# 01-100BASET1_PHY.net
KiCad netlist of a schematic drawn in Altium Designer
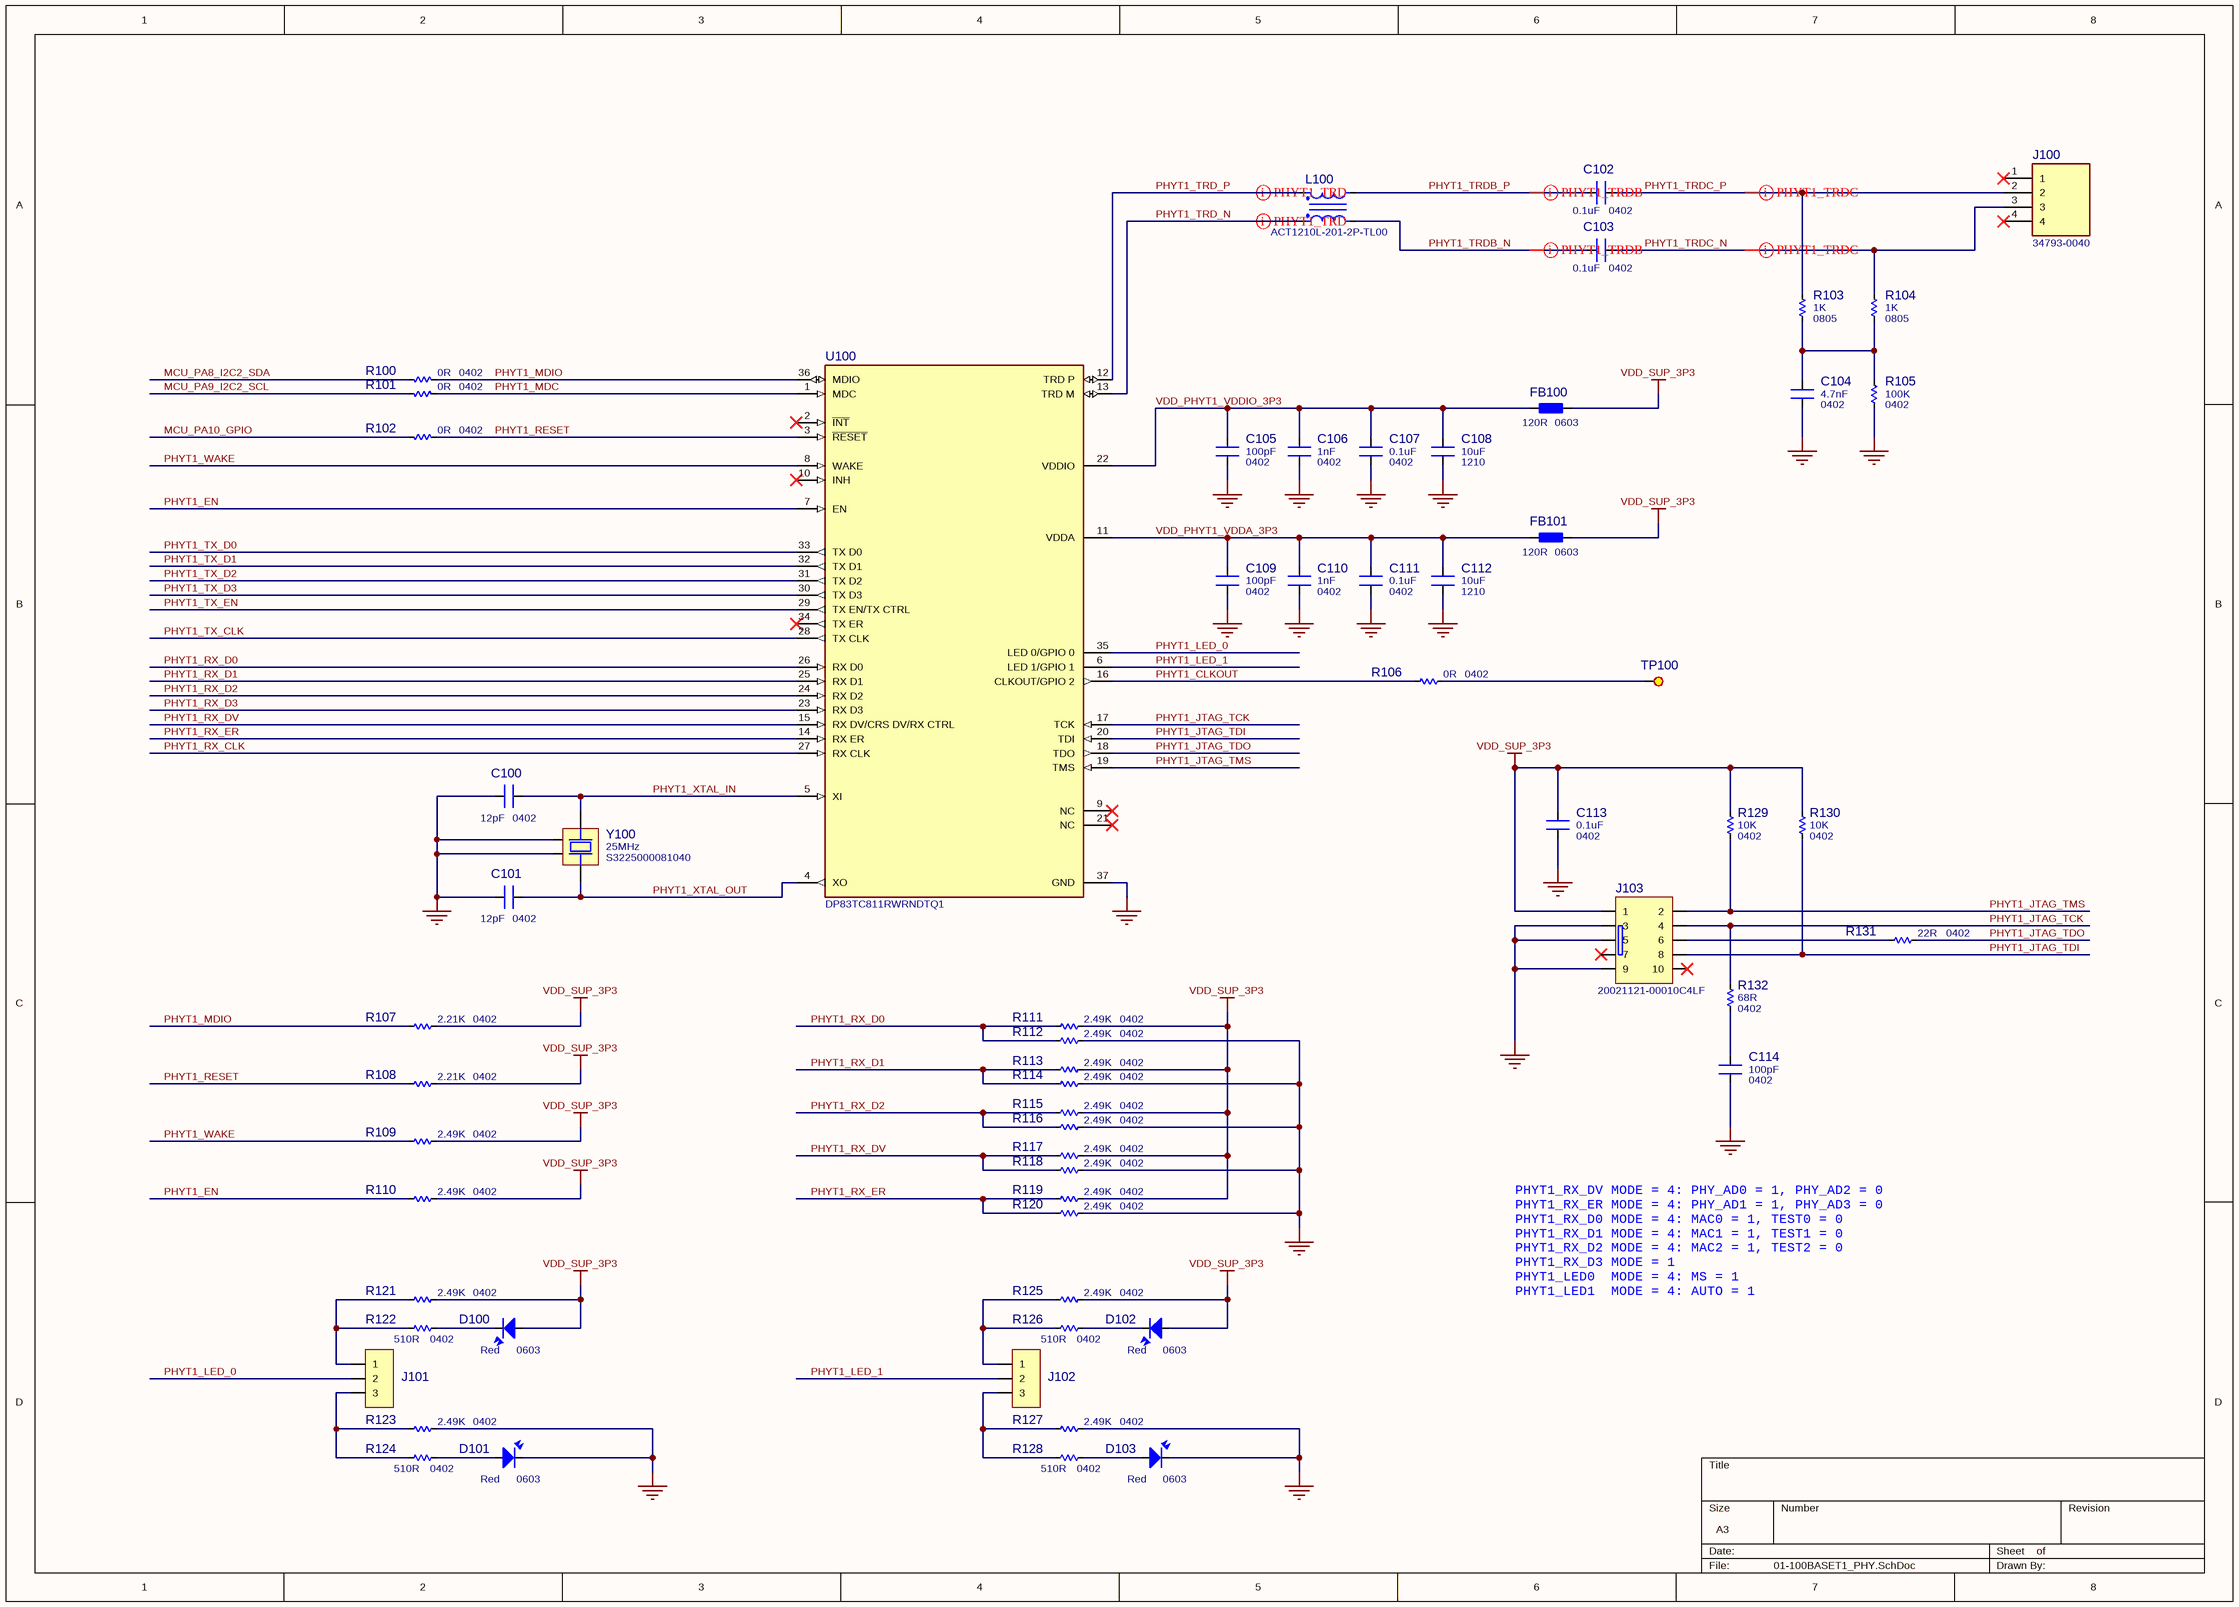
[diagram p0: 01-100BASET1_PHY.SchDoc]

(export (version "E")
  (design (tool "Eeschema 10.0.6"))
  (components
    (comp (ref "C100")
      (value "12pF")
      (footprint "CAP_C_0402")
      (description "Ceramic Capacitor SMD 0402 12pF ±5% 50V")
      (fields
        (field (name "TOLERANCE") "±5%")
        (field (name "MANUFACTURER") "FH(Guangdong Fenghua Advanced Tech)")
        (field (name "PACKAGE") "0402")
      )
      (libsource (lib "AS50") (part "Cap"))
    )
    (comp (ref "C101")
      (value "12pF")
      (footprint "CAP_C_0402")
      (description "Ceramic Capacitor SMD 0402 12pF ±5% 50V")
      (fields
        (field (name "TOLERANCE") "±5%")
        (field (name "MANUFACTURER") "FH(Guangdong Fenghua Advanced Tech)")
        (field (name "PACKAGE") "0402")
      )
      (libsource (lib "AS50") (part "Cap"))
    )
    (comp (ref "C102")
      (value "0.1uF")
      (footprint "CAP_C_0402")
      (description "Ceramic Capacitor SMD 0402 100nF ±10% 16V")
      (fields
        (field (name "TOLERANCE") "±10%")
        (field (name "MANUFACTURER") "Samsung")
        (field (name "PACKAGE") "0402")
      )
      (libsource (lib "AS50") (part "Cap"))
    )
    (comp (ref "C103")
      (value "0.1uF")
      (footprint "CAP_C_0402")
      (description "Ceramic Capacitor SMD 0402 100nF ±10% 16V")
      (fields
        (field (name "TOLERANCE") "±10%")
        (field (name "MANUFACTURER") "Samsung")
        (field (name "PACKAGE") "0402")
      )
      (libsource (lib "AS50") (part "Cap"))
    )
    (comp (ref "C104")
      (value "4.7nF")
      (footprint "CAP_C_0402")
      (description "Ceramic Capacitor SMD 0402 4.7nF ±10% 50V")
      (fields
        (field (name "TOLERANCE") "±10%")
        (field (name "MANUFACTURER") "FH(Guangdong Fenghua Advanced Tech)")
        (field (name "PACKAGE") "0402")
      )
      (libsource (lib "AS50") (part "Cap"))
    )
    (comp (ref "C105")
      (value "100pF")
      (footprint "CAP_C_0402")
      (description "Ceramic Capacitor SMD 0402 100pF ±5% 50V")
      (fields
        (field (name "TOLERANCE") "±5%")
        (field (name "MANUFACTURER") "Samsung")
        (field (name "PACKAGE") "0402")
      )
      (libsource (lib "AS50") (part "Cap"))
    )
    (comp (ref "C106")
      (value "1nF")
      (footprint "CAP_C_0402")
      (description "Ceramic Capacitor SMD 0402 1nF ±10% 50V")
      (fields
        (field (name "TOLERANCE") "±10%")
        (field (name "MANUFACTURER") "Samsung")
        (field (name "PACKAGE") "0402")
      )
      (libsource (lib "AS50") (part "Cap"))
    )
    (comp (ref "C107")
      (value "0.1uF")
      (footprint "CAP_C_0402")
      (description "Ceramic Capacitor SMD 0402 100nF ±10% 16V")
      (fields
        (field (name "TOLERANCE") "±10%")
        (field (name "MANUFACTURER") "Samsung")
        (field (name "PACKAGE") "0402")
      )
      (libsource (lib "AS50") (part "Cap"))
    )
    (comp (ref "C108")
      (value "10uF")
      (footprint "CAP_C_1210")
      (description "Ceramic Capacitor SMD 1210 10uF ±10% 25V")
      (fields
        (field (name "TOLERANCE") "±10%")
        (field (name "MANUFACTURER") "Samsung")
        (field (name "PACKAGE") "1210")
      )
      (libsource (lib "AS50") (part "Cap"))
    )
    (comp (ref "C109")
      (value "100pF")
      (footprint "CAP_C_0402")
      (description "Ceramic Capacitor SMD 0402 100pF ±5% 50V")
      (fields
        (field (name "TOLERANCE") "±5%")
        (field (name "MANUFACTURER") "Samsung")
        (field (name "PACKAGE") "0402")
      )
      (libsource (lib "AS50") (part "Cap"))
    )
    (comp (ref "C110")
      (value "1nF")
      (footprint "CAP_C_0402")
      (description "Ceramic Capacitor SMD 0402 1nF ±10% 50V")
      (fields
        (field (name "TOLERANCE") "±10%")
        (field (name "MANUFACTURER") "Samsung")
        (field (name "PACKAGE") "0402")
      )
      (libsource (lib "AS50") (part "Cap"))
    )
    (comp (ref "C111")
      (value "0.1uF")
      (footprint "CAP_C_0402")
      (description "Ceramic Capacitor SMD 0402 100nF ±10% 16V")
      (fields
        (field (name "TOLERANCE") "±10%")
        (field (name "MANUFACTURER") "Samsung")
        (field (name "PACKAGE") "0402")
      )
      (libsource (lib "AS50") (part "Cap"))
    )
    (comp (ref "C112")
      (value "10uF")
      (footprint "CAP_C_1210")
      (description "Ceramic Capacitor SMD 1210 10uF ±10% 25V")
      (fields
        (field (name "TOLERANCE") "±10%")
        (field (name "MANUFACTURER") "Samsung")
        (field (name "PACKAGE") "1210")
      )
      (libsource (lib "AS50") (part "Cap"))
    )
    (comp (ref "C113")
      (value "0.1uF")
      (footprint "CAP_C_0402")
      (description "Ceramic Capacitor SMD 0402 100nF ±10% 16V")
      (fields
        (field (name "TOLERANCE") "±10%")
        (field (name "MANUFACTURER") "Samsung")
        (field (name "PACKAGE") "0402")
      )
      (libsource (lib "AS50") (part "Cap"))
    )
    (comp (ref "C114")
      (value "100pF")
      (footprint "CAP_C_0402")
      (description "Ceramic Capacitor SMD 0402 100pF ±5% 50V")
      (fields
        (field (name "TOLERANCE") "±5%")
        (field (name "MANUFACTURER") "FH(Guangdong Fenghua Advanced Tech)")
        (field (name "PACKAGE") "0402")
      )
      (libsource (lib "AS50") (part "Cap"))
    )
    (comp (ref "D100")
      (value "LED")
      (footprint "LED-SMD-0603-RED")
      (description "Red 615~630nm 1.9~2.2V 0603 Light Emitting Diodes (LED) RoHS")
      (fields
        (field (name "MANUFACTURER") "Hubei KENTO Elec")
        (field (name "MANUFACTURER PART NUMBER") "KT-0603R")
        (field (name "COLOR") "Red")
        (field (name "PACKAGE") "0603")
      )
      (libsource (lib "AS50") (part "LED"))
    )
    (comp (ref "D101")
      (value "LED")
      (footprint "LED-SMD-0603-RED")
      (description "Red 615~630nm 1.9~2.2V 0603 Light Emitting Diodes (LED) RoHS")
      (fields
        (field (name "MANUFACTURER") "Hubei KENTO Elec")
        (field (name "MANUFACTURER PART NUMBER") "KT-0603R")
        (field (name "COLOR") "Red")
        (field (name "PACKAGE") "0603")
      )
      (libsource (lib "AS50") (part "LED"))
    )
    (comp (ref "D102")
      (value "LED")
      (footprint "LED-SMD-0603-RED")
      (description "Red 615~630nm 1.9~2.2V 0603 Light Emitting Diodes (LED) RoHS")
      (fields
        (field (name "MANUFACTURER") "Hubei KENTO Elec")
        (field (name "MANUFACTURER PART NUMBER") "KT-0603R")
        (field (name "COLOR") "Red")
        (field (name "PACKAGE") "0603")
      )
      (libsource (lib "AS50") (part "LED"))
    )
    (comp (ref "D103")
      (value "LED")
      (footprint "LED-SMD-0603-RED")
      (description "Red 615~630nm 1.9~2.2V 0603 Light Emitting Diodes (LED) RoHS")
      (fields
        (field (name "MANUFACTURER") "Hubei KENTO Elec")
        (field (name "MANUFACTURER PART NUMBER") "KT-0603R")
        (field (name "COLOR") "Red")
        (field (name "PACKAGE") "0603")
      )
      (libsource (lib "AS50") (part "LED"))
    )
    (comp (ref "FB100")
      (value "120R")
      (footprint "Inductors:IND_C_0603")
      (description "Ferrite bead SMD 0603 120Ω ±25% @ 100MHz DCR=0.03Ω 3A")
      (fields
        (field (name "MANUFACTURER") "Murata Electronics")
        (field (name "MANUFACTURER PART NUMBER") "BLM18KG121TH1D")
        (field (name "PACKAGE") "0603")
      )
      (libsource (lib "AS50") (part "Ferrite bead"))
    )
    (comp (ref "FB101")
      (value "120R")
      (footprint "Inductors:IND_C_0603")
      (description "Ferrite bead SMD 0603 120Ω ±25% @ 100MHz DCR=0.03Ω 3A")
      (fields
        (field (name "MANUFACTURER") "Murata Electronics")
        (field (name "MANUFACTURER PART NUMBER") "BLM18KG121TH1D")
        (field (name "PACKAGE") "0603")
      )
      (libsource (lib "AS50") (part "Ferrite bead"))
    )
    (comp (ref "J100")
      (value "34793-0040")
      (footprint "34793-0040")
      (description "Automotive Connectors 4P 1R MINI50 HEADER R/A UNSEALED BLACK")
      (fields (field (name "MANUFACTURER") "Molex") (field (name "MANUFACTURER PART NUMBER") "34793-0040"))
      (libsource (lib "AS50") (part "34793-0040"))
    )
    (comp (ref "J101")
      (value "JP3")
      (footprint "JP3-D1T")
      (description "Single 3-pin jumper")
      (libsource (lib "AS50") (part "JP3"))
    )
    (comp (ref "J102")
      (value "JP3")
      (footprint "JP3-D1T")
      (description "Single 3-pin jumper")
      (libsource (lib "AS50") (part "JP3"))
    )
    (comp (ref "J103")
      (value "IDE_10P")
      (footprint "IDE_1.27-SMD-10V_2")
      (description "Conn Unshrouded Header HDR 10 POS 1.27mm Solder ST Top Entry SMD Tube")
      (fields
        (field (name "MANUFACTURER") "Amphenol ICC")
        (field (name "MANUFACTURER PART NUMBER") "20021121-00010C4LF")
      )
      (libsource (lib "AS50") (part "IDE_10P"))
    )
    (comp (ref "L100")
      (value "Choke")
      (footprint "IND_ACT1210L-2P")
      (description "200 µH @ 100 kHz 2 Line Common Mode Choke Surface Mount 70mA DCR 5.5Ohm")
      (fields
        (field (name "MANUFACTURER") "TDK")
        (field (name "MANUFACTURER PART NUMBER") "ACT1210L-201-2P-TL00")
      )
      (libsource (lib "AS50") (part "Choke"))
    )
    (comp (ref "R100")
      (value "0R")
      (footprint "RES_C_0402")
      (description "Resistor SMD 0402 0R ±1% 1/16W")
      (fields (field (name "PACKAGE") "0402") (field (name "TOLERANCE") "±1%") (field (name "VOLTAGE") "50V"))
      (libsource (lib "AS50") (part "Res"))
    )
    (comp (ref "R101")
      (value "0R")
      (footprint "RES_C_0402")
      (description "Resistor SMD 0402 0R ±1% 1/16W")
      (fields (field (name "PACKAGE") "0402") (field (name "TOLERANCE") "±1%") (field (name "VOLTAGE") "50V"))
      (libsource (lib "AS50") (part "Res"))
    )
    (comp (ref "R102")
      (value "0R")
      (footprint "RES_C_0402")
      (description "Resistor SMD 0402 0R ±1% 1/16W")
      (fields (field (name "PACKAGE") "0402") (field (name "TOLERANCE") "±1%") (field (name "VOLTAGE") "50V"))
      (libsource (lib "AS50") (part "Res"))
    )
    (comp (ref "R103")
      (value "1K")
      (footprint "RES_C_0805")
      (description "Resistor SMD 0805 1K ±1% 1/8W")
      (fields (field (name "PACKAGE") "0805") (field (name "TOLERANCE") "±1%") (field (name "VOLTAGE") "50V"))
      (libsource (lib "AS50") (part "Res"))
    )
    (comp (ref "R104")
      (value "1K")
      (footprint "RES_C_0805")
      (description "Resistor SMD 0805 1K ±1% 1/8W")
      (fields (field (name "PACKAGE") "0805") (field (name "TOLERANCE") "±1%") (field (name "VOLTAGE") "50V"))
      (libsource (lib "AS50") (part "Res"))
    )
    (comp (ref "R105")
      (value "100K")
      (footprint "RES_C_0402")
      (description "Resistor SMD 0402 100K ±1% 1/16W")
      (fields (field (name "PACKAGE") "0402") (field (name "TOLERANCE") "±1%") (field (name "VOLTAGE") "50V"))
      (libsource (lib "AS50") (part "Res"))
    )
    (comp (ref "R106")
      (value "0R")
      (footprint "RES_C_0402")
      (description "Resistor SMD 0402 0R ±1% 1/16W")
      (fields (field (name "PACKAGE") "0402") (field (name "TOLERANCE") "±1%") (field (name "VOLTAGE") "50V"))
      (libsource (lib "AS50") (part "Res"))
    )
    (comp (ref "R107")
      (value "2.21K")
      (footprint "RES_C_0402")
      (description "Resistor SMD 0402 2.21K ±1% 1/16W")
      (fields (field (name "PACKAGE") "0402") (field (name "TOLERANCE") "±1%") (field (name "VOLTAGE") "50V"))
      (libsource (lib "AS50") (part "Res"))
    )
    (comp (ref "R108")
      (value "2.21K")
      (footprint "RES_C_0402")
      (description "Resistor SMD 0402 2.21K ±1% 1/16W")
      (fields (field (name "PACKAGE") "0402") (field (name "TOLERANCE") "±1%") (field (name "VOLTAGE") "50V"))
      (libsource (lib "AS50") (part "Res"))
    )
    (comp (ref "R109")
      (value "2.49K")
      (footprint "RES_C_0402")
      (description "Resistor SMD 0402 2.49K ±1% 1/16W")
      (fields (field (name "PACKAGE") "0402") (field (name "TOLERANCE") "±1%") (field (name "VOLTAGE") "50V"))
      (libsource (lib "AS50") (part "Res"))
    )
    (comp (ref "R110")
      (value "2.49K")
      (footprint "RES_C_0402")
      (description "Resistor SMD 0402 2.49K ±1% 1/16W")
      (fields (field (name "PACKAGE") "0402") (field (name "TOLERANCE") "±1%") (field (name "VOLTAGE") "50V"))
      (libsource (lib "AS50") (part "Res"))
    )
    (comp (ref "R111")
      (value "2.49K")
      (footprint "RES_C_0402")
      (description "Resistor SMD 0402 2.49K ±1% 1/16W")
      (fields (field (name "PACKAGE") "0402") (field (name "TOLERANCE") "±1%") (field (name "VOLTAGE") "50V"))
      (libsource (lib "AS50") (part "Res"))
    )
    (comp (ref "R112")
      (value "2.49K")
      (footprint "RES_C_0402")
      (description "Resistor SMD 0402 2.49K ±1% 1/16W")
      (fields (field (name "PACKAGE") "0402") (field (name "TOLERANCE") "±1%") (field (name "VOLTAGE") "50V"))
      (libsource (lib "AS50") (part "Res"))
    )
    (comp (ref "R113")
      (value "2.49K")
      (footprint "RES_C_0402")
      (description "Resistor SMD 0402 2.49K ±1% 1/16W")
      (fields (field (name "PACKAGE") "0402") (field (name "TOLERANCE") "±1%") (field (name "VOLTAGE") "50V"))
      (libsource (lib "AS50") (part "Res"))
    )
    (comp (ref "R114")
      (value "2.49K")
      (footprint "RES_C_0402")
      (description "Resistor SMD 0402 2.49K ±1% 1/16W")
      (fields (field (name "PACKAGE") "0402") (field (name "TOLERANCE") "±1%") (field (name "VOLTAGE") "50V"))
      (libsource (lib "AS50") (part "Res"))
    )
    (comp (ref "R115")
      (value "2.49K")
      (footprint "RES_C_0402")
      (description "Resistor SMD 0402 2.49K ±1% 1/16W")
      (fields (field (name "PACKAGE") "0402") (field (name "TOLERANCE") "±1%") (field (name "VOLTAGE") "50V"))
      (libsource (lib "AS50") (part "Res"))
    )
    (comp (ref "R116")
      (value "2.49K")
      (footprint "RES_C_0402")
      (description "Resistor SMD 0402 2.49K ±1% 1/16W")
      (fields (field (name "PACKAGE") "0402") (field (name "TOLERANCE") "±1%") (field (name "VOLTAGE") "50V"))
      (libsource (lib "AS50") (part "Res"))
    )
    (comp (ref "R117")
      (value "2.49K")
      (footprint "RES_C_0402")
      (description "Resistor SMD 0402 2.49K ±1% 1/16W")
      (fields (field (name "PACKAGE") "0402") (field (name "TOLERANCE") "±1%") (field (name "VOLTAGE") "50V"))
      (libsource (lib "AS50") (part "Res"))
    )
    (comp (ref "R118")
      (value "2.49K")
      (footprint "RES_C_0402")
      (description "Resistor SMD 0402 2.49K ±1% 1/16W")
      (fields (field (name "PACKAGE") "0402") (field (name "TOLERANCE") "±1%") (field (name "VOLTAGE") "50V"))
      (libsource (lib "AS50") (part "Res"))
    )
    (comp (ref "R119")
      (value "2.49K")
      (footprint "RES_C_0402")
      (description "Resistor SMD 0402 2.49K ±1% 1/16W")
      (fields (field (name "PACKAGE") "0402") (field (name "TOLERANCE") "±1%") (field (name "VOLTAGE") "50V"))
      (libsource (lib "AS50") (part "Res"))
    )
    (comp (ref "R120")
      (value "2.49K")
      (footprint "RES_C_0402")
      (description "Resistor SMD 0402 2.49K ±1% 1/16W")
      (fields (field (name "PACKAGE") "0402") (field (name "TOLERANCE") "±1%") (field (name "VOLTAGE") "50V"))
      (libsource (lib "AS50") (part "Res"))
    )
    (comp (ref "R121")
      (value "2.49K")
      (footprint "RES_C_0402")
      (description "Resistor SMD 0402 2.49K ±1% 1/16W")
      (fields (field (name "PACKAGE") "0402") (field (name "TOLERANCE") "±1%") (field (name "VOLTAGE") "50V"))
      (libsource (lib "AS50") (part "Res"))
    )
    (comp (ref "R122")
      (value "510R")
      (footprint "RES_C_0402")
      (description "Resistor SMD 0402 510R ±1% 1/16W")
      (fields (field (name "PACKAGE") "0402") (field (name "TOLERANCE") "±1%") (field (name "VOLTAGE") "50V"))
      (libsource (lib "AS50") (part "Res"))
    )
    (comp (ref "R123")
      (value "2.49K")
      (footprint "RES_C_0402")
      (description "Resistor SMD 0402 2.49K ±1% 1/16W")
      (fields (field (name "PACKAGE") "0402") (field (name "TOLERANCE") "±1%") (field (name "VOLTAGE") "50V"))
      (libsource (lib "AS50") (part "Res"))
    )
    (comp (ref "R124")
      (value "510R")
      (footprint "RES_C_0402")
      (description "Resistor SMD 0402 510R ±1% 1/16W")
      (fields (field (name "PACKAGE") "0402") (field (name "TOLERANCE") "±1%") (field (name "VOLTAGE") "50V"))
      (libsource (lib "AS50") (part "Res"))
    )
    (comp (ref "R125")
      (value "2.49K")
      (footprint "RES_C_0402")
      (description "Resistor SMD 0402 2.49K ±1% 1/16W")
      (fields (field (name "PACKAGE") "0402") (field (name "TOLERANCE") "±1%") (field (name "VOLTAGE") "50V"))
      (libsource (lib "AS50") (part "Res"))
    )
    (comp (ref "R126")
      (value "510R")
      (footprint "RES_C_0402")
      (description "Resistor SMD 0402 510R ±1% 1/16W")
      (fields (field (name "PACKAGE") "0402") (field (name "TOLERANCE") "±1%") (field (name "VOLTAGE") "50V"))
      (libsource (lib "AS50") (part "Res"))
    )
    (comp (ref "R127")
      (value "2.49K")
      (footprint "RES_C_0402")
      (description "Resistor SMD 0402 2.49K ±1% 1/16W")
      (fields (field (name "PACKAGE") "0402") (field (name "TOLERANCE") "±1%") (field (name "VOLTAGE") "50V"))
      (libsource (lib "AS50") (part "Res"))
    )
    (comp (ref "R128")
      (value "510R")
      (footprint "RES_C_0402")
      (description "Resistor SMD 0402 510R ±1% 1/16W")
      (fields (field (name "PACKAGE") "0402") (field (name "TOLERANCE") "±1%") (field (name "VOLTAGE") "50V"))
      (libsource (lib "AS50") (part "Res"))
    )
    (comp (ref "R129")
      (value "10K")
      (footprint "RES_C_0402")
      (description "Resistor SMD 0402 10K ±1% 1/16W")
      (fields (field (name "PACKAGE") "0402") (field (name "TOLERANCE") "±1%") (field (name "VOLTAGE") "50V"))
      (libsource (lib "AS50") (part "Res"))
    )
    (comp (ref "R130")
      (value "10K")
      (footprint "RES_C_0402")
      (description "Resistor SMD 0402 10K ±1% 1/16W")
      (fields (field (name "PACKAGE") "0402") (field (name "TOLERANCE") "±1%") (field (name "VOLTAGE") "50V"))
      (libsource (lib "AS50") (part "Res"))
    )
    (comp (ref "R131")
      (value "22R")
      (footprint "RES_C_0402")
      (description "Resistor SMD 0402 22R ±1% 1/16W")
      (fields (field (name "PACKAGE") "0402") (field (name "TOLERANCE") "±1%") (field (name "VOLTAGE") "50V"))
      (libsource (lib "AS50") (part "Res"))
    )
    (comp (ref "R132")
      (value "68R")
      (footprint "RES_C_0402")
      (description "Resistor SMD 0402 68R ±1% 1/16W")
      (fields (field (name "PACKAGE") "0402") (field (name "TOLERANCE") "±1%") (field (name "VOLTAGE") "50V"))
      (libsource (lib "AS50") (part "Res"))
    )
    (comp (ref "TP100")
      (value "TestPoint")
      (footprint "TESTPOINT")
      (description "Test Point")
      (libsource (lib "AS50") (part "TestPoint"))
    )
    (comp (ref "U100")
      (value "DP83TC811RWRNDTQ1")
      (footprint "QFN50P600X600X100_HS-37N")
      (fields
        (field (name "MANUFACTURER") "Texas Instruments")
        (field (name "MANUFACTURER PART NUMBER") "DP83TC811RWRNDTQ1")
      )
      (libsource (lib "AS50") (part "DP83TC811RWRNDTQ1"))
    )
    (comp (ref "Y100")
      (value "Crystal")
      (footprint "XT-SMD-3225-4P")
      (description "25MHz SMD Crystal Resonator 8pF 40Ω ±10ppm -40℃~+85℃ SMD3225-4P")
      (fields
        (field (name "MANUFACTURER") "JGHC")
        (field (name "MANUFACTURER PART NUMBER") "S3225000081040")
        (field (name "FREQUENCY") "25MHz")
      )
      (libsource (lib "AS50") (part "CX3225SB12000H0PSTC1"))
    )
  )
  (nets
    (net (code "1") (name "/MCU_PA8_I2C2_SDA") (class "Default")
      (node (ref "R100") (pin "2") (pinfunction "2_2") (pintype "passive"))
    )
    (net (code "2") (name "/MCU_PA9_I2C2_SCL") (class "Default")
      (node (ref "R101") (pin "2") (pinfunction "2_2") (pintype "passive"))
    )
    (net (code "3") (name "/MCU_PA10_GPIO") (class "Default")
      (node (ref "R102") (pin "2") (pinfunction "2_2") (pintype "passive"))
    )
    (net (code "4") (name "/PHYT1_CLKOUT") (class "Default")
      (node (ref "R106") (pin "2") (pinfunction "2_2") (pintype "passive"))
      (node (ref "U100") (pin "16") (pinfunction "CLKOUT/GPIO_2_16") (pintype "output"))
    )
    (net (code "5") (name "/PHYT1_EN") (class "Default")
      (node (ref "R110") (pin "1") (pinfunction "1_1") (pintype "passive"))
      (node (ref "U100") (pin "7") (pinfunction "EN_7") (pintype "input"))
    )
    (net (code "6") (name "/PHYT1_JTAG_TCK") (class "Default")
      (node (ref "J103") (pin "4") (pinfunction "4_4") (pintype "passive"))
      (node (ref "R132") (pin "1") (pinfunction "1_1") (pintype "passive"))
      (node (ref "U100") (pin "17") (pinfunction "TCK_17") (pintype "input"))
    )
    (net (code "7") (name "/PHYT1_JTAG_TDI") (class "Default")
      (node (ref "J103") (pin "8") (pinfunction "8_8") (pintype "passive"))
      (node (ref "R130") (pin "2") (pinfunction "2_2") (pintype "passive"))
      (node (ref "U100") (pin "20") (pinfunction "TDI_20") (pintype "input"))
    )
    (net (code "8") (name "/PHYT1_JTAG_TDO") (class "Default")
      (node (ref "R131") (pin "1") (pinfunction "1_1") (pintype "passive"))
      (node (ref "U100") (pin "18") (pinfunction "TDO_18") (pintype "output"))
    )
    (net (code "9") (name "/PHYT1_JTAG_TMS") (class "Default")
      (node (ref "J103") (pin "2") (pinfunction "2_2") (pintype "passive"))
      (node (ref "R129") (pin "2") (pinfunction "2_2") (pintype "passive"))
      (node (ref "U100") (pin "19") (pinfunction "TMS_19") (pintype "input"))
    )
    (net (code "10") (name "/PHYT1_LED_0") (class "Default")
      (node (ref "J101") (pin "2") (pinfunction "2_2") (pintype "passive"))
      (node (ref "U100") (pin "35") (pinfunction "LED_0/GPIO_0_35") (pintype "passive"))
    )
    (net (code "11") (name "/PHYT1_LED_1") (class "Default")
      (node (ref "J102") (pin "2") (pinfunction "2_2") (pintype "passive"))
      (node (ref "U100") (pin "6") (pinfunction "LED_1/GPIO_1_6") (pintype "passive"))
    )
    (net (code "12") (name "/PHYT1_MDC") (class "Default")
      (node (ref "R101") (pin "1") (pinfunction "1_1") (pintype "passive"))
      (node (ref "U100") (pin "1") (pinfunction "MDC_1") (pintype "input"))
    )
    (net (code "13") (name "/PHYT1_MDIO") (class "Default")
      (node (ref "R100") (pin "1") (pinfunction "1_1") (pintype "passive"))
      (node (ref "R107") (pin "1") (pinfunction "1_1") (pintype "passive"))
      (node (ref "U100") (pin "36") (pinfunction "MDIO_36") (pintype "bidirectional"))
    )
    (net (code "14") (name "/PHYT1_RESET") (class "Default")
      (node (ref "R102") (pin "1") (pinfunction "1_1") (pintype "passive"))
      (node (ref "R108") (pin "1") (pinfunction "1_1") (pintype "passive"))
      (node (ref "U100") (pin "3") (pinfunction "~{RESET}_3") (pintype "input"))
    )
    (net (code "15") (name "/PHYT1_RX_CLK") (class "Default")
      (node (ref "U100") (pin "27") (pinfunction "RX_CLK_27") (pintype "input"))
    )
    (net (code "16") (name "/PHYT1_RX_D0") (class "Default")
      (node (ref "R111") (pin "1") (pinfunction "1_1") (pintype "passive"))
      (node (ref "R112") (pin "1") (pinfunction "1_1") (pintype "passive"))
      (node (ref "U100") (pin "26") (pinfunction "RX_D0_26") (pintype "input"))
    )
    (net (code "17") (name "/PHYT1_RX_D1") (class "Default")
      (node (ref "R113") (pin "1") (pinfunction "1_1") (pintype "passive"))
      (node (ref "R114") (pin "1") (pinfunction "1_1") (pintype "passive"))
      (node (ref "U100") (pin "25") (pinfunction "RX_D1_25") (pintype "input"))
    )
    (net (code "18") (name "/PHYT1_RX_D2") (class "Default")
      (node (ref "R115") (pin "1") (pinfunction "1_1") (pintype "passive"))
      (node (ref "R116") (pin "1") (pinfunction "1_1") (pintype "passive"))
      (node (ref "U100") (pin "24") (pinfunction "RX_D2_24") (pintype "input"))
    )
    (net (code "19") (name "/PHYT1_RX_D3") (class "Default")
      (node (ref "U100") (pin "23") (pinfunction "RX_D3_23") (pintype "input"))
    )
    (net (code "20") (name "/PHYT1_RX_DV") (class "Default")
      (node (ref "R117") (pin "1") (pinfunction "1_1") (pintype "passive"))
      (node (ref "R118") (pin "1") (pinfunction "1_1") (pintype "passive"))
      (node (ref "U100") (pin "15") (pinfunction "RX_DV/CRS_DV/RX_CTRL_15") (pintype "input"))
    )
    (net (code "21") (name "/PHYT1_RX_ER") (class "Default")
      (node (ref "R119") (pin "1") (pinfunction "1_1") (pintype "passive"))
      (node (ref "R120") (pin "1") (pinfunction "1_1") (pintype "passive"))
      (node (ref "U100") (pin "14") (pinfunction "RX_ER_14") (pintype "input"))
    )
    (net (code "22") (name "/PHYT1_TRDB_N") (class "Default")
      (node (ref "C103") (pin "2") (pinfunction "2_2") (pintype "passive"))
      (node (ref "L100") (pin "4") (pinfunction "4_4") (pintype "passive"))
    )
    (net (code "23") (name "/PHYT1_TRDB_P") (class "Default")
      (node (ref "C102") (pin "2") (pinfunction "2_2") (pintype "passive"))
      (node (ref "L100") (pin "3") (pinfunction "3_3") (pintype "passive"))
    )
    (net (code "24") (name "/PHYT1_TRDC_N") (class "Default")
      (node (ref "C103") (pin "1") (pinfunction "1_1") (pintype "passive"))
      (node (ref "J100") (pin "3") (pinfunction "3_3") (pintype "passive"))
      (node (ref "R104") (pin "2") (pinfunction "2_2") (pintype "passive"))
    )
    (net (code "25") (name "/PHYT1_TRDC_P") (class "Default")
      (node (ref "C102") (pin "1") (pinfunction "1_1") (pintype "passive"))
      (node (ref "J100") (pin "2") (pinfunction "2_2") (pintype "passive"))
      (node (ref "R103") (pin "2") (pinfunction "2_2") (pintype "passive"))
    )
    (net (code "26") (name "/PHYT1_TRD_N") (class "Default")
      (node (ref "L100") (pin "1") (pinfunction "1_1") (pintype "passive"))
      (node (ref "U100") (pin "13") (pinfunction "TRD_M_13") (pintype "bidirectional"))
    )
    (net (code "27") (name "/PHYT1_TRD_P") (class "Default")
      (node (ref "L100") (pin "2") (pinfunction "2_2") (pintype "passive"))
      (node (ref "U100") (pin "12") (pinfunction "TRD_P_12") (pintype "bidirectional"))
    )
    (net (code "28") (name "/PHYT1_TX_CLK") (class "Default")
      (node (ref "U100") (pin "28") (pinfunction "TX_CLK_28") (pintype "output"))
    )
    (net (code "29") (name "/PHYT1_TX_D0") (class "Default")
      (node (ref "U100") (pin "33") (pinfunction "TX_D0_33") (pintype "output"))
    )
    (net (code "30") (name "/PHYT1_TX_D1") (class "Default")
      (node (ref "U100") (pin "32") (pinfunction "TX_D1_32") (pintype "output"))
    )
    (net (code "31") (name "/PHYT1_TX_D2") (class "Default")
      (node (ref "U100") (pin "31") (pinfunction "TX_D2_31") (pintype "output"))
    )
    (net (code "32") (name "/PHYT1_TX_D3") (class "Default")
      (node (ref "U100") (pin "30") (pinfunction "TX_D3_30") (pintype "output"))
    )
    (net (code "33") (name "/PHYT1_TX_EN") (class "Default")
      (node (ref "U100") (pin "29") (pinfunction "TX_EN/TX_CTRL_29") (pintype "output"))
    )
    (net (code "34") (name "/PHYT1_WAKE") (class "Default")
      (node (ref "R109") (pin "1") (pinfunction "1_1") (pintype "passive"))
      (node (ref "U100") (pin "8") (pinfunction "WAKE_8") (pintype "input"))
    )
    (net (code "35") (name "/PHYT1_XTAL_IN") (class "Default")
      (node (ref "C100") (pin "1") (pinfunction "1_1") (pintype "passive"))
      (node (ref "U100") (pin "5") (pinfunction "XI_5") (pintype "input"))
      (node (ref "Y100") (pin "1") (pinfunction "1_1") (pintype "passive"))
    )
    (net (code "36") (name "/PHYT1_XTAL_OUT") (class "Default")
      (node (ref "C101") (pin "1") (pinfunction "1_1") (pintype "passive"))
      (node (ref "U100") (pin "4") (pinfunction "XO_4") (pintype "output"))
      (node (ref "Y100") (pin "3") (pinfunction "3_3") (pintype "passive"))
    )
    (net (code "37") (name "/VDD_PHYT1_VDDA_3P3") (class "Default")
      (node (ref "C109") (pin "2") (pinfunction "2_2") (pintype "passive"))
      (node (ref "C110") (pin "2") (pinfunction "2_2") (pintype "passive"))
      (node (ref "C111") (pin "2") (pinfunction "2_2") (pintype "passive"))
      (node (ref "C112") (pin "2") (pinfunction "2_2") (pintype "passive"))
      (node (ref "FB101") (pin "2") (pinfunction "2_2") (pintype "passive"))
      (node (ref "U100") (pin "11") (pinfunction "VDDA_11") (pintype "power_in"))
    )
    (net (code "38") (name "/VDD_PHYT1_VDDIO_3P3") (class "Default")
      (node (ref "C105") (pin "2") (pinfunction "2_2") (pintype "passive"))
      (node (ref "C106") (pin "2") (pinfunction "2_2") (pintype "passive"))
      (node (ref "C107") (pin "2") (pinfunction "2_2") (pintype "passive"))
      (node (ref "C108") (pin "2") (pinfunction "2_2") (pintype "passive"))
      (node (ref "FB100") (pin "2") (pinfunction "2_2") (pintype "passive"))
      (node (ref "U100") (pin "22") (pinfunction "VDDIO_22") (pintype "power_in"))
    )
    (net (code "39") (name "GND") (class "Default")
      (node (ref "C100") (pin "2") (pinfunction "2_2") (pintype "passive"))
      (node (ref "C101") (pin "2") (pinfunction "2_2") (pintype "passive"))
      (node (ref "C104") (pin "2") (pinfunction "2_2") (pintype "passive"))
      (node (ref "C105") (pin "1") (pinfunction "1_1") (pintype "passive"))
      (node (ref "C106") (pin "1") (pinfunction "1_1") (pintype "passive"))
      (node (ref "C107") (pin "1") (pinfunction "1_1") (pintype "passive"))
      (node (ref "C108") (pin "1") (pinfunction "1_1") (pintype "passive"))
      (node (ref "C109") (pin "1") (pinfunction "1_1") (pintype "passive"))
      (node (ref "C110") (pin "1") (pinfunction "1_1") (pintype "passive"))
      (node (ref "C111") (pin "1") (pinfunction "1_1") (pintype "passive"))
      (node (ref "C112") (pin "1") (pinfunction "1_1") (pintype "passive"))
      (node (ref "C113") (pin "1") (pinfunction "1_1") (pintype "passive"))
      (node (ref "C114") (pin "2") (pinfunction "2_2") (pintype "passive"))
      (node (ref "D101") (pin "2") (pinfunction "2_2") (pintype "passive"))
      (node (ref "D103") (pin "2") (pinfunction "2_2") (pintype "passive"))
      (node (ref "J103") (pin "3") (pinfunction "3_3") (pintype "passive"))
      (node (ref "J103") (pin "5") (pinfunction "5_5") (pintype "passive"))
      (node (ref "J103") (pin "9") (pinfunction "9_9") (pintype "passive"))
      (node (ref "R105") (pin "2") (pinfunction "2_2") (pintype "passive"))
      (node (ref "R112") (pin "2") (pinfunction "2_2") (pintype "passive"))
      (node (ref "R114") (pin "2") (pinfunction "2_2") (pintype "passive"))
      (node (ref "R116") (pin "2") (pinfunction "2_2") (pintype "passive"))
      (node (ref "R118") (pin "2") (pinfunction "2_2") (pintype "passive"))
      (node (ref "R120") (pin "2") (pinfunction "2_2") (pintype "passive"))
      (node (ref "R123") (pin "2") (pinfunction "2_2") (pintype "passive"))
      (node (ref "R127") (pin "2") (pinfunction "2_2") (pintype "passive"))
      (node (ref "U100") (pin "37") (pinfunction "GND_37") (pintype "power_in"))
      (node (ref "Y100") (pin "2") (pinfunction "2_2") (pintype "power_in"))
      (node (ref "Y100") (pin "4") (pinfunction "4_4") (pintype "power_in"))
    )
    (net (code "40") (name "Net-(C104-Pad1)") (class "Default")
      (node (ref "C104") (pin "1") (pinfunction "1_1") (pintype "passive"))
      (node (ref "R103") (pin "1") (pinfunction "1_1") (pintype "passive"))
      (node (ref "R104") (pin "1") (pinfunction "1_1") (pintype "passive"))
      (node (ref "R105") (pin "1") (pinfunction "1_1") (pintype "passive"))
    )
    (net (code "41") (name "Net-(C114-Pad1)") (class "Default")
      (node (ref "C114") (pin "1") (pinfunction "1_1") (pintype "passive"))
      (node (ref "R132") (pin "2") (pinfunction "2_2") (pintype "passive"))
    )
    (net (code "42") (name "Net-(D100-Pad2)") (class "Default")
      (node (ref "D100") (pin "2") (pinfunction "2_2") (pintype "passive"))
      (node (ref "R122") (pin "2") (pinfunction "2_2") (pintype "passive"))
    )
    (net (code "43") (name "Net-(D101-Pad1)") (class "Default")
      (node (ref "D101") (pin "1") (pinfunction "1_1") (pintype "passive"))
      (node (ref "R124") (pin "2") (pinfunction "2_2") (pintype "passive"))
    )
    (net (code "44") (name "Net-(D102-Pad2)") (class "Default")
      (node (ref "D102") (pin "2") (pinfunction "2_2") (pintype "passive"))
      (node (ref "R126") (pin "2") (pinfunction "2_2") (pintype "passive"))
    )
    (net (code "45") (name "Net-(D103-Pad1)") (class "Default")
      (node (ref "D103") (pin "1") (pinfunction "1_1") (pintype "passive"))
      (node (ref "R128") (pin "2") (pinfunction "2_2") (pintype "passive"))
    )
    (net (code "46") (name "Net-(J101-Pad1)") (class "Default")
      (node (ref "J101") (pin "1") (pinfunction "1_1") (pintype "passive"))
      (node (ref "R121") (pin "1") (pinfunction "1_1") (pintype "passive"))
      (node (ref "R122") (pin "1") (pinfunction "1_1") (pintype "passive"))
    )
    (net (code "47") (name "Net-(J101-Pad3)") (class "Default")
      (node (ref "J101") (pin "3") (pinfunction "3_3") (pintype "passive"))
      (node (ref "R123") (pin "1") (pinfunction "1_1") (pintype "passive"))
      (node (ref "R124") (pin "1") (pinfunction "1_1") (pintype "passive"))
    )
    (net (code "48") (name "Net-(J102-Pad1)") (class "Default")
      (node (ref "J102") (pin "1") (pinfunction "1_1") (pintype "passive"))
      (node (ref "R125") (pin "1") (pinfunction "1_1") (pintype "passive"))
      (node (ref "R126") (pin "1") (pinfunction "1_1") (pintype "passive"))
    )
    (net (code "49") (name "Net-(J102-Pad3)") (class "Default")
      (node (ref "J102") (pin "3") (pinfunction "3_3") (pintype "passive"))
      (node (ref "R127") (pin "1") (pinfunction "1_1") (pintype "passive"))
      (node (ref "R128") (pin "1") (pinfunction "1_1") (pintype "passive"))
    )
    (net (code "50") (name "Net-(J103-Pad6)") (class "Default")
      (node (ref "J103") (pin "6") (pinfunction "6_6") (pintype "passive"))
      (node (ref "R131") (pin "2") (pinfunction "2_2") (pintype "passive"))
    )
    (net (code "51") (name "Net-(R106-Pad1)") (class "Default")
      (node (ref "R106") (pin "1") (pinfunction "1_1") (pintype "passive"))
      (node (ref "TP100") (pin "0") (pintype "passive"))
    )
    (net (code "52") (name "VDD_SUP_3P3") (class "Default")
      (node (ref "C113") (pin "2") (pinfunction "2_2") (pintype "passive"))
      (node (ref "D100") (pin "1") (pinfunction "1_1") (pintype "passive"))
      (node (ref "D102") (pin "1") (pinfunction "1_1") (pintype "passive"))
      (node (ref "FB100") (pin "1") (pinfunction "1_1") (pintype "passive"))
      (node (ref "FB101") (pin "1") (pinfunction "1_1") (pintype "passive"))
      (node (ref "J103") (pin "1") (pinfunction "1_1") (pintype "passive"))
      (node (ref "R107") (pin "2") (pinfunction "2_2") (pintype "passive"))
      (node (ref "R108") (pin "2") (pinfunction "2_2") (pintype "passive"))
      (node (ref "R109") (pin "2") (pinfunction "2_2") (pintype "passive"))
      (node (ref "R110") (pin "2") (pinfunction "2_2") (pintype "passive"))
      (node (ref "R111") (pin "2") (pinfunction "2_2") (pintype "passive"))
      (node (ref "R113") (pin "2") (pinfunction "2_2") (pintype "passive"))
      (node (ref "R115") (pin "2") (pinfunction "2_2") (pintype "passive"))
      (node (ref "R117") (pin "2") (pinfunction "2_2") (pintype "passive"))
      (node (ref "R119") (pin "2") (pinfunction "2_2") (pintype "passive"))
      (node (ref "R121") (pin "2") (pinfunction "2_2") (pintype "passive"))
      (node (ref "R125") (pin "2") (pinfunction "2_2") (pintype "passive"))
      (node (ref "R129") (pin "1") (pinfunction "1_1") (pintype "passive"))
      (node (ref "R130") (pin "1") (pinfunction "1_1") (pintype "passive"))
    )
    (net (code "53") (name "unconnected-(J100-Pad1)") (class "Default")
      (node (ref "J100") (pin "1") (pinfunction "1_1") (pintype "passive+no_connect"))
    )
    (net (code "54") (name "unconnected-(J100-Pad4)") (class "Default")
      (node (ref "J100") (pin "4") (pinfunction "4_4") (pintype "passive+no_connect"))
    )
    (net (code "55") (name "unconnected-(J103-Pad7)") (class "Default")
      (node (ref "J103") (pin "7") (pinfunction "7_7") (pintype "passive+no_connect"))
    )
    (net (code "56") (name "unconnected-(J103-Pad10)") (class "Default")
      (node (ref "J103") (pin "10") (pinfunction "10_10") (pintype "passive+no_connect"))
    )
    (net (code "57") (name "unconnected-(U100-INH-Pad10)") (class "Default")
      (node (ref "U100") (pin "10") (pinfunction "INH_10") (pintype "input+no_connect"))
    )
    (net (code "58") (name "unconnected-(U100-NC-Pad9)") (class "Default")
      (node (ref "U100") (pin "9") (pinfunction "NC_9") (pintype "passive+no_connect"))
    )
    (net (code "59") (name "unconnected-(U100-NC-Pad21)") (class "Default")
      (node (ref "U100") (pin "21") (pinfunction "NC_21") (pintype "passive+no_connect"))
    )
    (net (code "60") (name "unconnected-(U100-TX_ER-Pad34)") (class "Default")
      (node (ref "U100") (pin "34") (pinfunction "TX_ER_34") (pintype "output+no_connect"))
    )
    (net (code "61") (name "unconnected-(U100-~{INT}-Pad2)") (class "Default")
      (node (ref "U100") (pin "2") (pinfunction "~{INT}_2") (pintype "input+no_connect"))
    )
  )
)
